# ICM20600.net
KiCad netlist of a schematic drawn in EAGLE
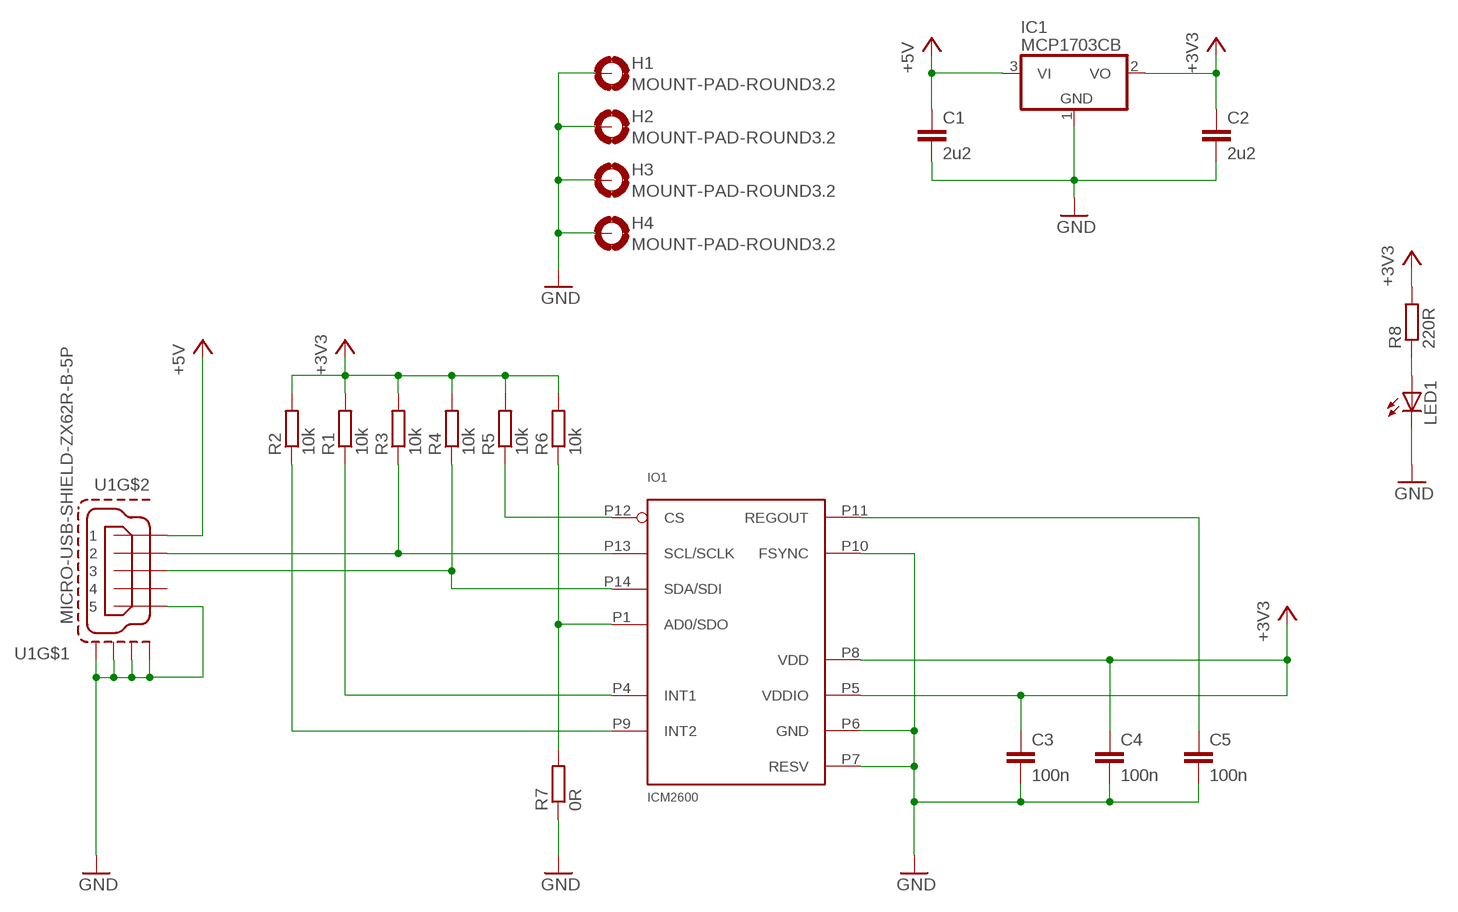
[diagram p0: schematic, sheet 1]

(export (version "E")
  (design (tool "Eeschema 10.0.6"))
  (components
    (comp (ref "C1")
      (value "2u2")
      (footprint "eagle-import:C0603")
      (libsource (lib "eagle-import") (part "C-EUC0603"))
    )
    (comp (ref "C2")
      (value "2u2")
      (footprint "eagle-import:C0603")
      (libsource (lib "eagle-import") (part "C-EUC0603"))
    )
    (comp (ref "C3")
      (value "100n")
      (footprint "eagle-import:C0603")
      (libsource (lib "eagle-import") (part "C-EUC0603"))
    )
    (comp (ref "C4")
      (value "100n")
      (footprint "eagle-import:C0603")
      (libsource (lib "eagle-import") (part "C-EUC0603"))
    )
    (comp (ref "C5")
      (value "100n")
      (footprint "eagle-import:C0603")
      (libsource (lib "eagle-import") (part "C-EUC0603"))
    )
    (comp (ref "H1")
      (value "MOUNT-PAD-ROUND3.2")
      (footprint "eagle-import:3,2-PAD")
      (libsource (lib "eagle-import") (part "MOUNT-PAD-ROUND3.2"))
    )
    (comp (ref "H2")
      (value "MOUNT-PAD-ROUND3.2")
      (footprint "eagle-import:3,2-PAD")
      (libsource (lib "eagle-import") (part "MOUNT-PAD-ROUND3.2"))
    )
    (comp (ref "H3")
      (value "MOUNT-PAD-ROUND3.2")
      (footprint "eagle-import:3,2-PAD")
      (libsource (lib "eagle-import") (part "MOUNT-PAD-ROUND3.2"))
    )
    (comp (ref "H4")
      (value "MOUNT-PAD-ROUND3.2")
      (footprint "eagle-import:3,2-PAD")
      (libsource (lib "eagle-import") (part "MOUNT-PAD-ROUND3.2"))
    )
    (comp (ref "IC1")
      (value "MCP1703CB")
      (footprint "eagle-import:SOT23")
      (libsource (lib "eagle-import") (part "MCP1703CB"))
    )
    (comp (ref "IO1")
      (value "ICM2600")
      (footprint "eagle-import:LGA14")
      (libsource (lib "eagle-import") (part "ICM20600"))
    )
    (comp (ref "LED1")
      (value "LEDSML0603")
      (footprint "eagle-import:SML0603")
      (libsource (lib "eagle-import") (part "LEDSML0603"))
    )
    (comp (ref "R1")
      (value "10k")
      (footprint "eagle-import:R0603")
      (libsource (lib "eagle-import") (part "R-EU_R0603"))
    )
    (comp (ref "R2")
      (value "10k")
      (footprint "eagle-import:R0603")
      (libsource (lib "eagle-import") (part "R-EU_R0603"))
    )
    (comp (ref "R3")
      (value "10k")
      (footprint "eagle-import:R0603")
      (libsource (lib "eagle-import") (part "R-EU_R0603"))
    )
    (comp (ref "R4")
      (value "10k")
      (footprint "eagle-import:R0603")
      (libsource (lib "eagle-import") (part "R-EU_R0603"))
    )
    (comp (ref "R5")
      (value "10k")
      (footprint "eagle-import:R0603")
      (libsource (lib "eagle-import") (part "R-EU_R0603"))
    )
    (comp (ref "R6")
      (value "10k")
      (footprint "eagle-import:R0603")
      (libsource (lib "eagle-import") (part "R-EU_R0603"))
    )
    (comp (ref "R7")
      (value "0R")
      (footprint "eagle-import:R0603")
      (libsource (lib "eagle-import") (part "R-EU_R0603"))
    )
    (comp (ref "R8")
      (value "220R")
      (footprint "eagle-import:R0603")
      (libsource (lib "eagle-import") (part "R-EU_R0603"))
    )
    (comp (ref "U1")
      (value "MICRO-USB-SHIELD-ZX62R-B-5P")
      (footprint "eagle-import:ZX62R-B-5P")
      (libsource (lib "eagle-import") (part "MICRO-USB-SHIELD-ZX62R-B-5P"))
    )
  )
  (nets
    (net (code "1") (name "+3V3") (class "Default")
      (node (ref "C2") (pin "1") (pinfunction "1_1") (pintype "passive"))
      (node (ref "C3") (pin "1") (pinfunction "1_1") (pintype "passive"))
      (node (ref "C4") (pin "1") (pinfunction "1_1") (pintype "passive"))
      (node (ref "IC1") (pin "2") (pinfunction "VO_2") (pintype "passive"))
      (node (ref "IO1") (pin "P5") (pinfunction "VDDIO_P5") (pintype "power_in"))
      (node (ref "IO1") (pin "P8") (pinfunction "VDD_P8") (pintype "power_in"))
      (node (ref "R1") (pin "2") (pinfunction "2_2") (pintype "passive"))
      (node (ref "R2") (pin "2") (pinfunction "2_2") (pintype "passive"))
      (node (ref "R3") (pin "2") (pinfunction "2_2") (pintype "passive"))
      (node (ref "R4") (pin "2") (pinfunction "2_2") (pintype "passive"))
      (node (ref "R5") (pin "2") (pinfunction "2_2") (pintype "passive"))
      (node (ref "R6") (pin "2") (pinfunction "2_2") (pintype "passive"))
      (node (ref "R8") (pin "2") (pinfunction "2_2") (pintype "passive"))
    )
    (net (code "2") (name "+5V") (class "Default")
      (node (ref "C1") (pin "1") (pinfunction "1_1") (pintype "passive"))
      (node (ref "IC1") (pin "3") (pinfunction "VI_3") (pintype "input"))
      (node (ref "U1") (pin "1") (pinfunction "1_1") (pintype "input"))
    )
    (net (code "3") (name "GND") (class "Default")
      (node (ref "C1") (pin "2") (pinfunction "2_2") (pintype "passive"))
      (node (ref "C2") (pin "2") (pinfunction "2_2") (pintype "passive"))
      (node (ref "C3") (pin "2") (pinfunction "2_2") (pintype "passive"))
      (node (ref "C4") (pin "2") (pinfunction "2_2") (pintype "passive"))
      (node (ref "C5") (pin "2") (pinfunction "2_2") (pintype "passive"))
      (node (ref "H1") (pin "B3,2") (pinfunction "MOUNT_B3,2") (pintype "passive"))
      (node (ref "H2") (pin "B3,2") (pinfunction "MOUNT_B3,2") (pintype "passive"))
      (node (ref "H3") (pin "B3,2") (pinfunction "MOUNT_B3,2") (pintype "passive"))
      (node (ref "H4") (pin "B3,2") (pinfunction "MOUNT_B3,2") (pintype "passive"))
      (node (ref "IC1") (pin "1") (pinfunction "GND_1") (pintype "passive"))
      (node (ref "IO1") (pin "P10") (pinfunction "FSYNC_P10") (pintype "input"))
      (node (ref "IO1") (pin "P6") (pinfunction "GND_P6") (pintype "power_in"))
      (node (ref "IO1") (pin "P7") (pinfunction "RESV_P7") (pintype "passive"))
      (node (ref "LED1") (pin "C") (pinfunction "C_C") (pintype "passive"))
      (node (ref "R7") (pin "1") (pinfunction "1_1") (pintype "passive"))
      (node (ref "U1") (pin "5") (pinfunction "5_5") (pintype "input"))
      (node (ref "U1") (pin "M1") (pinfunction "S1_M1") (pintype "passive"))
      (node (ref "U1") (pin "M2") (pinfunction "S2_M2") (pintype "passive"))
      (node (ref "U1") (pin "M3") (pinfunction "S3_M3") (pintype "passive"))
      (node (ref "U1") (pin "M4") (pinfunction "S4_M4") (pintype "passive"))
    )
    (net (code "4") (name "Net-(IO1-AD0{slash}SDO)") (class "Default")
      (node (ref "IO1") (pin "P1") (pinfunction "AD0/SDO_P1") (pintype "output"))
      (node (ref "R6") (pin "1") (pinfunction "1_1") (pintype "passive"))
      (node (ref "R7") (pin "2") (pinfunction "2_2") (pintype "passive"))
    )
    (net (code "5") (name "Net-(IO1-CS)") (class "Default")
      (node (ref "IO1") (pin "P12") (pinfunction "CS_P12") (pintype "output"))
      (node (ref "R5") (pin "1") (pinfunction "1_1") (pintype "passive"))
    )
    (net (code "6") (name "Net-(IO1-INT1)") (class "Default")
      (node (ref "IO1") (pin "P4") (pinfunction "INT1_P4") (pintype "output"))
      (node (ref "R1") (pin "1") (pinfunction "1_1") (pintype "passive"))
    )
    (net (code "7") (name "Net-(IO1-INT2)") (class "Default")
      (node (ref "IO1") (pin "P9") (pinfunction "INT2_P9") (pintype "output"))
      (node (ref "R2") (pin "1") (pinfunction "1_1") (pintype "passive"))
    )
    (net (code "8") (name "Net-(IO1-REGOUT)") (class "Default")
      (node (ref "C5") (pin "1") (pinfunction "1_1") (pintype "passive"))
      (node (ref "IO1") (pin "P11") (pinfunction "REGOUT_P11") (pintype "output"))
    )
    (net (code "9") (name "Net-(IO1-SCL{slash}SCLK)") (class "Default")
      (node (ref "IO1") (pin "P13") (pinfunction "SCL/SCLK_P13") (pintype "bidirectional"))
      (node (ref "R3") (pin "1") (pinfunction "1_1") (pintype "passive"))
      (node (ref "U1") (pin "2") (pinfunction "2_2") (pintype "input"))
    )
    (net (code "10") (name "Net-(IO1-SDA{slash}SDI)") (class "Default")
      (node (ref "IO1") (pin "P14") (pinfunction "SDA/SDI_P14") (pintype "bidirectional"))
      (node (ref "R4") (pin "1") (pinfunction "1_1") (pintype "passive"))
      (node (ref "U1") (pin "3") (pinfunction "3_3") (pintype "input"))
    )
    (net (code "11") (name "Net-(LED1-PadA)") (class "Default")
      (node (ref "LED1") (pin "A") (pinfunction "A_A") (pintype "passive"))
      (node (ref "R8") (pin "1") (pinfunction "1_1") (pintype "passive"))
    )
    (net (code "12") (name "unconnected-(U1-Pad4)") (class "Default")
      (node (ref "U1") (pin "4") (pinfunction "4_4") (pintype "input"))
    )
  )
)
